# Connectors.net
KiCad netlist of a schematic drawn in Altium Designer
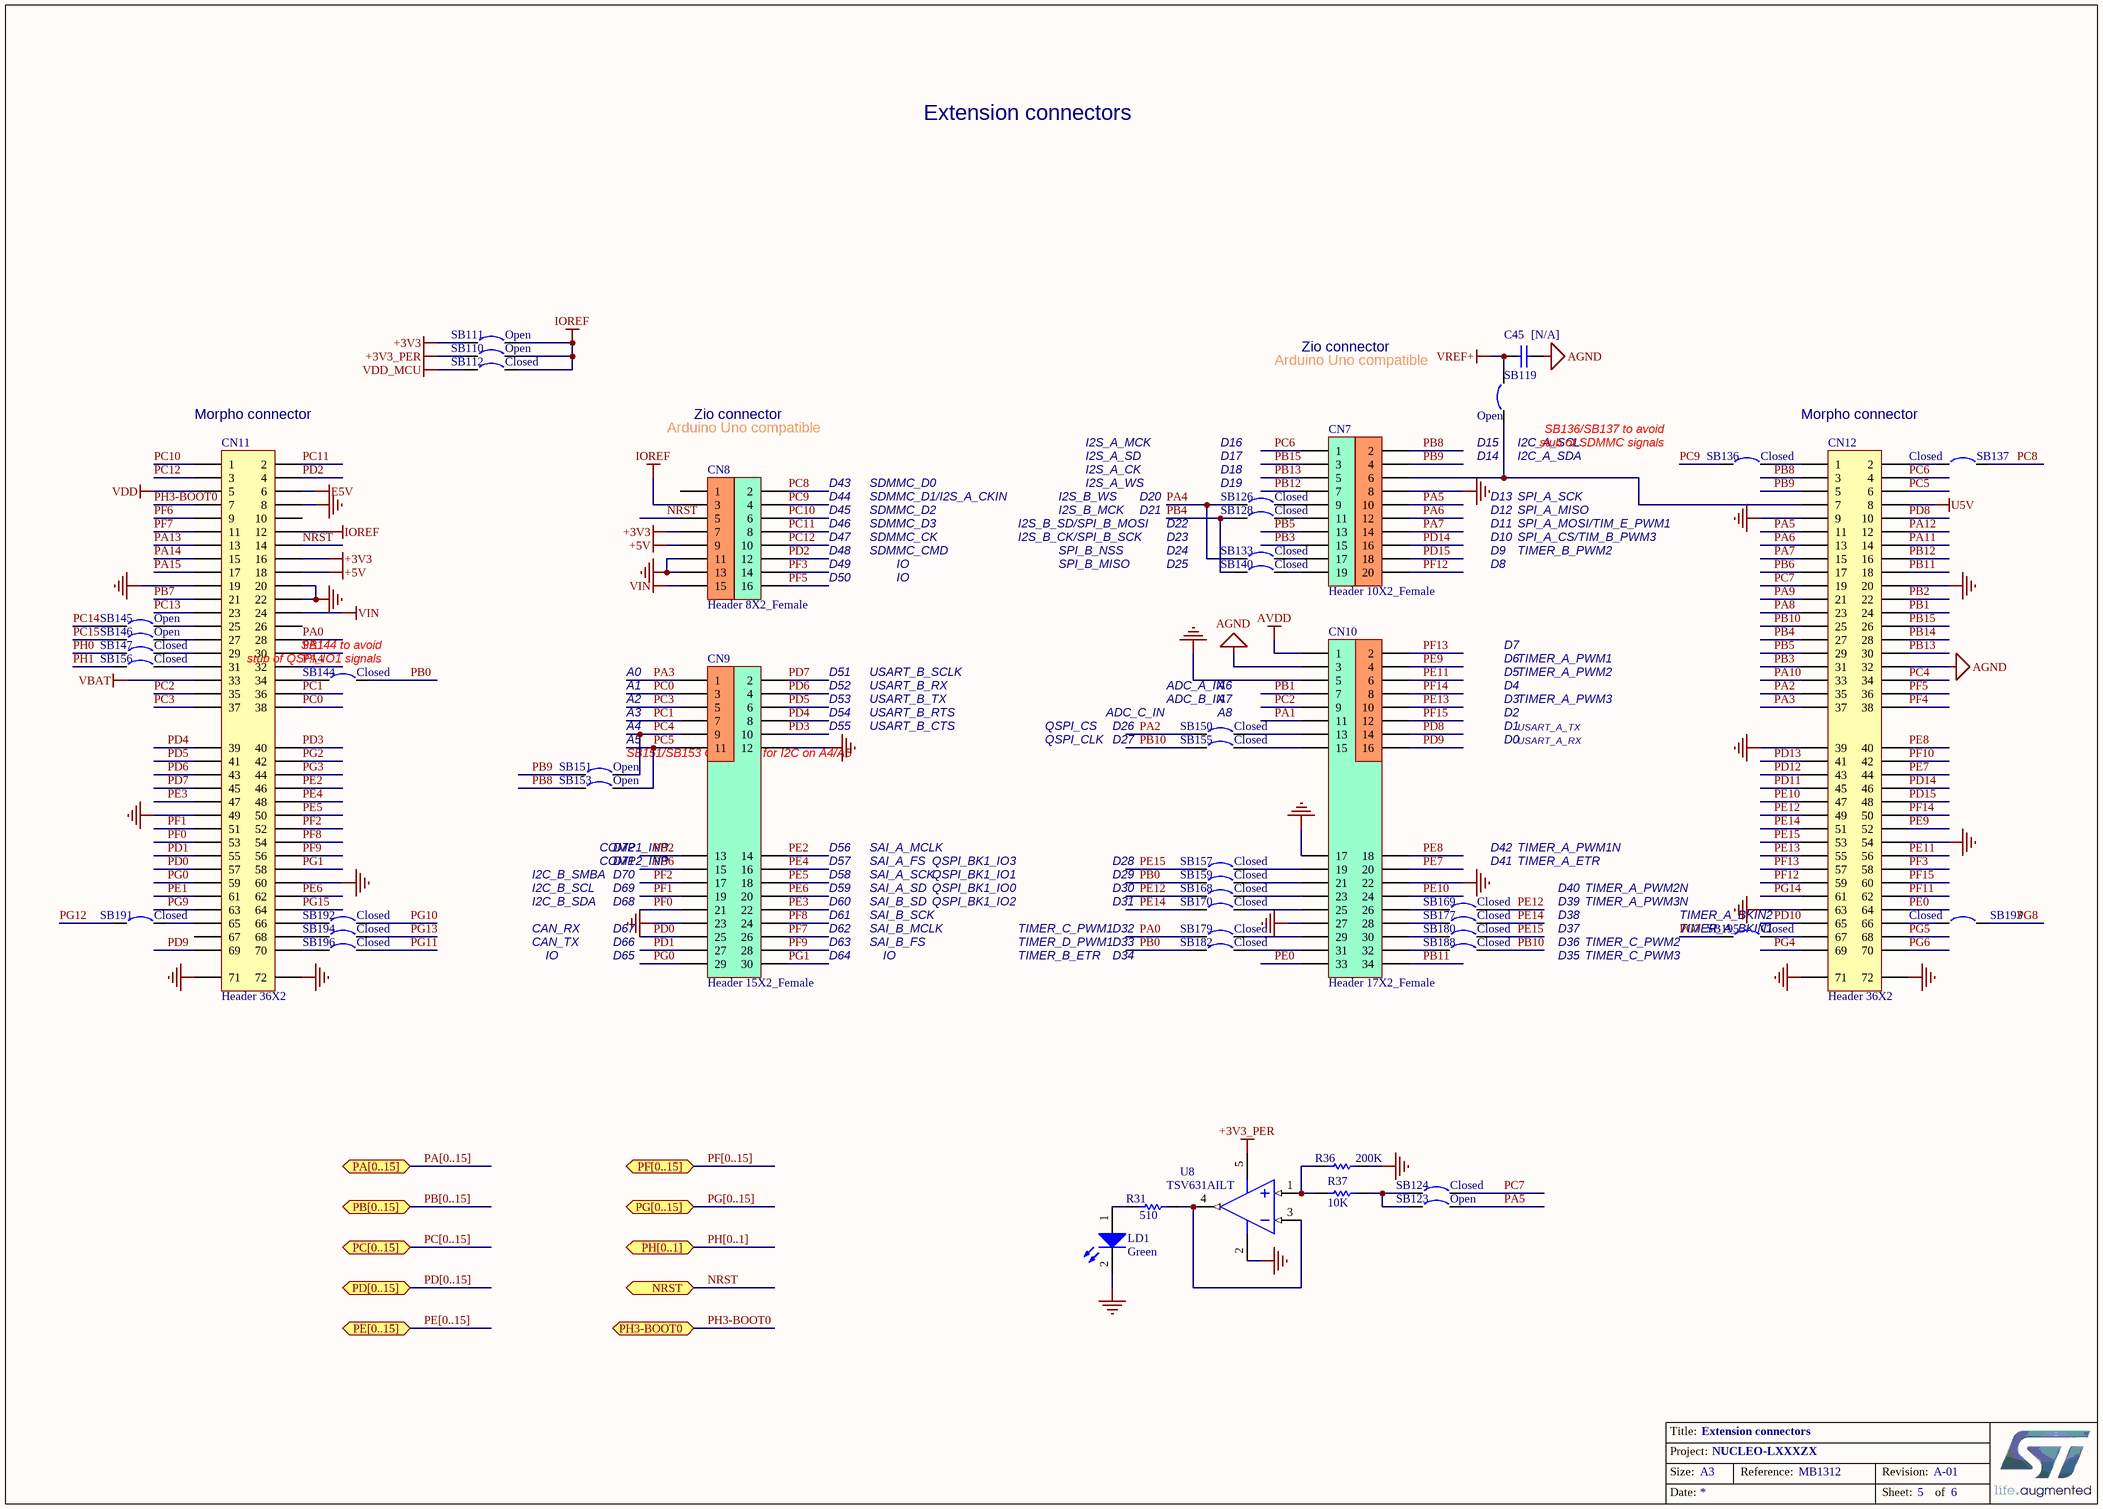
[diagram p0: Connectors.SchDoc]

(export (version "E")
  (design (tool "Eeschema 10.0.6"))
  (components
    (comp (ref "C45")
      (value "[N/A]")
      (footprint "0603C")
      (description "Capacitor,100nF,10%,16V,X7R,0603,YAGEO")
      (fields (field (name "PUBLISHER") "Altium Limited"))
      (libsource (lib "Miscellaneous Devices") (part "Cap"))
    )
    (comp (ref "CN7")
      (value "Header 10X2_Female")
      (footprint "HDR_10x2_2R54_V_F")
      (description "Header, 10-Pin, Dual row,female")
      (fields (field (name "PUBLISHER") "Altium Limited"))
      (libsource (lib "MB1137") (part "Header 10X2_Female"))
    )
    (comp (ref "CN8")
      (value "Header 8X2_Female")
      (footprint "HDR_8x2_2R54_V_F")
      (description "Header, 8-Pin, Dual row,female")
      (fields (field (name "PUBLISHER") "Altium Limited"))
      (libsource (lib "MB1137") (part "Header 8X2_Female"))
    )
    (comp (ref "CN9")
      (value "Header 15X2_Female")
      (footprint "HDR_15x2_2R54_V_F")
      (description "Header, 15-Pin, Dual row,female")
      (fields (field (name "PUBLISHER") "Altium Limited"))
      (libsource (lib "MB1137") (part "Header 15X2_Female"))
    )
    (comp (ref "CN10")
      (value "Header 17X2_Female")
      (footprint "HDR_17x2_2R54_V_F")
      (description "Header, 17-Pin, Dual row,female")
      (fields (field (name "PUBLISHER") "Altium Limited"))
      (libsource (lib "MB1137") (part "Header 17X2_Female"))
    )
    (comp (ref "CN11")
      (value "Header 36X2")
      (footprint "HDR_2x36_2R54_V_M")
      (description "Header, 36-Pin, Dual row")
      (fields (field (name "PUBLISHER") "Altium Limited"))
      (libsource (lib "MB1137") (part "Header 36X2"))
    )
    (comp (ref "CN12")
      (value "Header 36X2")
      (footprint "HDR_2x36_2R54_V_M")
      (description "Header, 36-Pin, Dual row")
      (fields (field (name "PUBLISHER") "Altium Limited"))
      (libsource (lib "MB1137") (part "Header 36X2"))
    )
    (comp (ref "LD1")
      (value "Green")
      (footprint "0603D-G")
      (description "Typical RED, GREEN, YELLOW, AMBER GaAs LED")
      (fields (field (name "PUBLISHER") "Altium Limited"))
      (libsource (lib "Miscellaneous Devices") (part "LED2"))
    )
    (comp (ref "R31")
      (value "510")
      (footprint "0603R")
      (description "Resistor")
      (fields (field (name "PUBLISHER") "Altium Limited"))
      (libsource (lib "Miscellaneous Devices") (part "Res1"))
    )
    (comp (ref "R36")
      (value "200K")
      (footprint "0603R")
      (description "Resistor")
      (fields (field (name "PUBLISHER") "Altium Limited"))
      (libsource (lib "Miscellaneous Devices") (part "res1"))
    )
    (comp (ref "R37")
      (value "10K")
      (footprint "0603R")
      (description "Resistor")
      (fields (field (name "PUBLISHER") "Altium Limited"))
      (libsource (lib "Miscellaneous Devices") (part "res1"))
    )
    (comp (ref "SB110")
      (value "Open")
      (footprint "SB_0603")
      (description "Circuit Breaker")
      (fields (field (name "PUBLISHER") "Altium Limited"))
      (libsource (lib "") (part "Circuit Breaker_1"))
    )
    (comp (ref "SB111")
      (value "Open")
      (footprint "SB_0603")
      (description "Circuit Breaker")
      (fields (field (name "PUBLISHER") "Altium Limited"))
      (libsource (lib "") (part "Circuit Breaker_1"))
    )
    (comp (ref "SB112")
      (value "Closed")
      (footprint "SB_0603")
      (description "Circuit Breaker")
      (fields (field (name "PUBLISHER") "Altium Limited"))
      (libsource (lib "MB1167") (part "Circuit Breaker_close"))
    )
    (comp (ref "SB119")
      (value "Open")
      (footprint "SB_0603")
      (description "Circuit Breaker")
      (fields (field (name "PUBLISHER") "Altium Limited"))
      (libsource (lib "MB1167") (part "Circuit Breaker"))
    )
    (comp (ref "SB123")
      (value "Open")
      (footprint "SB_0603")
      (description "Circuit Breaker")
      (fields (field (name "PUBLISHER") "Altium Limited"))
      (libsource (lib "") (part "Circuit Breaker_1"))
    )
    (comp (ref "SB124")
      (value "Closed")
      (footprint "SB_0603")
      (description "Circuit Breaker")
      (fields (field (name "PUBLISHER") "Altium Limited"))
      (libsource (lib "") (part "Circuit Breaker_close_1"))
    )
    (comp (ref "SB126")
      (value "Closed")
      (footprint "SB_0603")
      (description "Circuit Breaker")
      (fields (field (name "PUBLISHER") "Altium Limited"))
      (libsource (lib "MB1167") (part "Circuit Breaker_close"))
    )
    (comp (ref "SB128")
      (value "Closed")
      (footprint "SB_0603")
      (description "Circuit Breaker")
      (fields (field (name "PUBLISHER") "Altium Limited"))
      (libsource (lib "MB1167") (part "Circuit Breaker_close"))
    )
    (comp (ref "SB133")
      (value "Closed")
      (footprint "SB_0603")
      (description "Circuit Breaker")
      (fields (field (name "PUBLISHER") "Altium Limited"))
      (libsource (lib "MB1167") (part "Circuit Breaker_close"))
    )
    (comp (ref "SB136")
      (value "Closed")
      (footprint "SB_0603")
      (description "Circuit Breaker")
      (fields (field (name "PUBLISHER") "Altium Limited"))
      (libsource (lib "MB1167") (part "Circuit Breaker_close"))
    )
    (comp (ref "SB137")
      (value "Closed")
      (footprint "SB_0603")
      (description "Circuit Breaker")
      (fields (field (name "PUBLISHER") "Altium Limited"))
      (libsource (lib "") (part "Circuit Breaker_close_1"))
    )
    (comp (ref "SB140")
      (value "Closed")
      (footprint "SB_0603")
      (description "Circuit Breaker")
      (fields (field (name "PUBLISHER") "Altium Limited"))
      (libsource (lib "MB1167") (part "Circuit Breaker_close"))
    )
    (comp (ref "SB144")
      (value "Closed")
      (footprint "SB_0603")
      (description "Circuit Breaker")
      (fields (field (name "PUBLISHER") "Altium Limited"))
      (libsource (lib "MB1167") (part "Circuit Breaker_close"))
    )
    (comp (ref "SB145")
      (value "Open")
      (footprint "SB_0603")
      (description "Circuit Breaker")
      (fields (field (name "PUBLISHER") "Altium Limited"))
      (libsource (lib "") (part "Circuit Breaker_1"))
    )
    (comp (ref "SB146")
      (value "Open")
      (footprint "SB_0603")
      (description "Circuit Breaker")
      (fields (field (name "PUBLISHER") "Altium Limited"))
      (libsource (lib "") (part "Circuit Breaker_1"))
    )
    (comp (ref "SB147")
      (value "Closed")
      (footprint "SB_0603")
      (description "Circuit Breaker")
      (fields (field (name "PUBLISHER") "Altium Limited"))
      (libsource (lib "MB1167") (part "Circuit Breaker_close"))
    )
    (comp (ref "SB150")
      (value "Closed")
      (footprint "SB_0603")
      (description "Circuit Breaker")
      (fields (field (name "PUBLISHER") "Altium Limited"))
      (libsource (lib "MB1167") (part "Circuit Breaker_close"))
    )
    (comp (ref "SB151")
      (value "Open")
      (footprint "SB_0603")
      (description "Circuit Breaker")
      (fields (field (name "PUBLISHER") "Altium Limited"))
      (libsource (lib "") (part "Circuit Breaker_2"))
    )
    (comp (ref "SB153")
      (value "Open")
      (footprint "SB_0603")
      (description "Circuit Breaker")
      (fields (field (name "PUBLISHER") "Altium Limited"))
      (libsource (lib "") (part "Circuit Breaker_2"))
    )
    (comp (ref "SB155")
      (value "Closed")
      (footprint "SB_0603")
      (description "Circuit Breaker")
      (fields (field (name "PUBLISHER") "Altium Limited"))
      (libsource (lib "MB1167") (part "Circuit Breaker_close"))
    )
    (comp (ref "SB156")
      (value "Closed")
      (footprint "SB_0603")
      (description "Circuit Breaker")
      (fields (field (name "PUBLISHER") "Altium Limited"))
      (libsource (lib "MB1167") (part "Circuit Breaker_close"))
    )
    (comp (ref "SB157")
      (value "Closed")
      (footprint "SB_0603")
      (description "Circuit Breaker")
      (fields (field (name "PUBLISHER") "Altium Limited"))
      (libsource (lib "MB1167") (part "Circuit Breaker_close"))
    )
    (comp (ref "SB159")
      (value "Closed")
      (footprint "SB_0603")
      (description "Circuit Breaker")
      (fields (field (name "PUBLISHER") "Altium Limited"))
      (libsource (lib "MB1167") (part "Circuit Breaker_close"))
    )
    (comp (ref "SB168")
      (value "Closed")
      (footprint "SB_0603")
      (description "Circuit Breaker")
      (fields (field (name "PUBLISHER") "Altium Limited"))
      (libsource (lib "MB1167") (part "Circuit Breaker_close"))
    )
    (comp (ref "SB169")
      (value "Closed")
      (footprint "SB_0603")
      (description "Circuit Breaker")
      (fields (field (name "PUBLISHER") "Altium Limited"))
      (libsource (lib "MB1167") (part "Circuit Breaker_close"))
    )
    (comp (ref "SB170")
      (value "Closed")
      (footprint "SB_0603")
      (description "Circuit Breaker")
      (fields (field (name "PUBLISHER") "Altium Limited"))
      (libsource (lib "MB1167") (part "Circuit Breaker_close"))
    )
    (comp (ref "SB177")
      (value "Closed")
      (footprint "SB_0603")
      (description "Circuit Breaker")
      (fields (field (name "PUBLISHER") "Altium Limited"))
      (libsource (lib "MB1167") (part "Circuit Breaker_close"))
    )
    (comp (ref "SB179")
      (value "Closed")
      (footprint "SB_0603")
      (description "Circuit Breaker")
      (fields (field (name "PUBLISHER") "Altium Limited"))
      (libsource (lib "MB1167") (part "Circuit Breaker_close"))
    )
    (comp (ref "SB180")
      (value "Closed")
      (footprint "SB_0603")
      (description "Circuit Breaker")
      (fields (field (name "PUBLISHER") "Altium Limited"))
      (libsource (lib "MB1167") (part "Circuit Breaker_close"))
    )
    (comp (ref "SB182")
      (value "Closed")
      (footprint "SB_0603")
      (description "Circuit Breaker")
      (fields (field (name "PUBLISHER") "Altium Limited"))
      (libsource (lib "MB1167") (part "Circuit Breaker_close"))
    )
    (comp (ref "SB188")
      (value "Closed")
      (footprint "SB_0603")
      (description "Circuit Breaker")
      (fields (field (name "PUBLISHER") "Altium Limited"))
      (libsource (lib "MB1167") (part "Circuit Breaker_close"))
    )
    (comp (ref "SB191")
      (value "Closed")
      (footprint "SB_0603")
      (description "Circuit Breaker")
      (fields (field (name "PUBLISHER") "Altium Limited"))
      (libsource (lib "MB1167") (part "Circuit Breaker_close"))
    )
    (comp (ref "SB192")
      (value "Closed")
      (footprint "SB_0603")
      (description "Circuit Breaker")
      (fields (field (name "PUBLISHER") "Altium Limited"))
      (libsource (lib "MB1167") (part "Circuit Breaker_close"))
    )
    (comp (ref "SB193")
      (value "Closed")
      (footprint "SB_0603")
      (description "Circuit Breaker")
      (fields (field (name "PUBLISHER") "Altium Limited"))
      (libsource (lib "MB1167") (part "Circuit Breaker_close"))
    )
    (comp (ref "SB194")
      (value "Closed")
      (footprint "SB_0603")
      (description "Circuit Breaker")
      (fields (field (name "PUBLISHER") "Altium Limited"))
      (libsource (lib "MB1167") (part "Circuit Breaker_close"))
    )
    (comp (ref "SB195")
      (value "Closed")
      (footprint "SB_0603")
      (description "Circuit Breaker")
      (fields (field (name "PUBLISHER") "Altium Limited"))
      (libsource (lib "MB1167") (part "Circuit Breaker_close"))
    )
    (comp (ref "SB196")
      (value "Closed")
      (footprint "SB_0603")
      (description "Circuit Breaker")
      (fields (field (name "PUBLISHER") "Altium Limited"))
      (libsource (lib "MB1167") (part "Circuit Breaker_close"))
    )
    (comp (ref "U8")
      (value "TSV631AILT")
      (footprint "SOT-23-5L")
      (libsource (lib "MB988") (part "TSV631AILT"))
    )
  )
  (nets
    (net (code "1") (name "+3V3") (class "Default")
      (node (ref "CN11") (pin "16") (pinfunction "16_16") (pintype "passive"))
      (node (ref "CN8") (pin "7") (pinfunction "7_7") (pintype "passive"))
      (node (ref "SB111") (pin "1") (pinfunction "1_1") (pintype "passive"))
    )
    (net (code "2") (name "+3V3_PER") (class "Default")
      (node (ref "SB110") (pin "1") (pinfunction "1_1") (pintype "passive"))
      (node (ref "U8") (pin "5") (pinfunction "VCC_5") (pintype "power_in"))
    )
    (net (code "3") (name "+5V") (class "Default")
      (node (ref "CN11") (pin "18") (pinfunction "18_18") (pintype "passive"))
      (node (ref "CN8") (pin "9") (pinfunction "9_9") (pintype "passive"))
    )
    (net (code "4") (name "/NRST") (class "Default")
      (node (ref "CN11") (pin "14") (pinfunction "14_14") (pintype "passive"))
      (node (ref "CN8") (pin "5") (pinfunction "5_5") (pintype "passive"))
    )
    (net (code "5") (name "/PA0") (class "Default")
      (node (ref "CN11") (pin "28") (pinfunction "28_28") (pintype "passive"))
      (node (ref "SB179") (pin "1") (pinfunction "1_1") (pintype "passive"))
    )
    (net (code "6") (name "/PA1") (class "Default")
      (node (ref "CN10") (pin "11") (pinfunction "11_11") (pintype "passive"))
      (node (ref "CN11") (pin "30") (pinfunction "30_30") (pintype "passive"))
    )
    (net (code "7") (name "/PA2") (class "Default")
      (node (ref "CN12") (pin "35") (pinfunction "35_35") (pintype "passive"))
      (node (ref "SB150") (pin "1") (pinfunction "1_1") (pintype "passive"))
    )
    (net (code "8") (name "/PA3") (class "Default")
      (node (ref "CN12") (pin "37") (pinfunction "37_37") (pintype "passive"))
      (node (ref "CN9") (pin "1") (pinfunction "1_1") (pintype "passive"))
    )
    (net (code "9") (name "/PA4") (class "Default")
      (node (ref "CN11") (pin "32") (pinfunction "32_32") (pintype "passive"))
      (node (ref "SB126") (pin "1") (pinfunction "1_1") (pintype "passive"))
      (node (ref "SB133") (pin "1") (pinfunction "1_1") (pintype "passive"))
    )
    (net (code "10") (name "/PA5") (class "Default")
      (node (ref "CN12") (pin "11") (pinfunction "11_11") (pintype "passive"))
      (node (ref "CN7") (pin "10") (pinfunction "10_10") (pintype "passive"))
      (node (ref "SB123") (pin "2") (pinfunction "2_2") (pintype "passive"))
    )
    (net (code "11") (name "/PA6") (class "Default")
      (node (ref "CN12") (pin "13") (pinfunction "13_13") (pintype "passive"))
      (node (ref "CN7") (pin "12") (pinfunction "12_12") (pintype "passive"))
    )
    (net (code "12") (name "/PA7") (class "Default")
      (node (ref "CN12") (pin "15") (pinfunction "15_15") (pintype "passive"))
      (node (ref "CN7") (pin "14") (pinfunction "14_14") (pintype "passive"))
    )
    (net (code "13") (name "/PA8") (class "Default")
      (node (ref "CN12") (pin "23") (pinfunction "23_23") (pintype "passive"))
    )
    (net (code "14") (name "/PA9") (class "Default")
      (node (ref "CN12") (pin "21") (pinfunction "21_21") (pintype "passive"))
    )
    (net (code "15") (name "/PA10") (class "Default")
      (node (ref "CN12") (pin "33") (pinfunction "33_33") (pintype "passive"))
    )
    (net (code "16") (name "/PA11") (class "Default")
      (node (ref "CN12") (pin "14") (pinfunction "14_14") (pintype "passive"))
    )
    (net (code "17") (name "/PA12") (class "Default")
      (node (ref "CN12") (pin "12") (pinfunction "12_12") (pintype "passive"))
    )
    (net (code "18") (name "/PA13") (class "Default")
      (node (ref "CN11") (pin "13") (pinfunction "13_13") (pintype "passive"))
    )
    (net (code "19") (name "/PA14") (class "Default")
      (node (ref "CN11") (pin "15") (pinfunction "15_15") (pintype "passive"))
    )
    (net (code "20") (name "/PA15") (class "Default")
      (node (ref "CN11") (pin "17") (pinfunction "17_17") (pintype "passive"))
    )
    (net (code "22") (name "/PB0") (class "Default")
      (node (ref "SB144") (pin "2") (pinfunction "2_2") (pintype "passive"))
      (node (ref "SB159") (pin "1") (pinfunction "1_1") (pintype "passive"))
      (node (ref "SB182") (pin "1") (pinfunction "1_1") (pintype "passive"))
    )
    (net (code "23") (name "/PB1") (class "Default")
      (node (ref "CN10") (pin "7") (pinfunction "7_7") (pintype "passive"))
      (node (ref "CN12") (pin "24") (pinfunction "24_24") (pintype "passive"))
    )
    (net (code "24") (name "/PB2") (class "Default")
      (node (ref "CN12") (pin "22") (pinfunction "22_22") (pintype "passive"))
      (node (ref "CN9") (pin "13") (pinfunction "13_13") (pintype "passive"))
    )
    (net (code "25") (name "/PB3") (class "Default")
      (node (ref "CN12") (pin "31") (pinfunction "31_31") (pintype "passive"))
      (node (ref "CN7") (pin "15") (pinfunction "15_15") (pintype "passive"))
    )
    (net (code "26") (name "/PB4") (class "Default")
      (node (ref "CN12") (pin "27") (pinfunction "27_27") (pintype "passive"))
      (node (ref "SB128") (pin "1") (pinfunction "1_1") (pintype "passive"))
      (node (ref "SB140") (pin "1") (pinfunction "1_1") (pintype "passive"))
    )
    (net (code "27") (name "/PB5") (class "Default")
      (node (ref "CN12") (pin "29") (pinfunction "29_29") (pintype "passive"))
      (node (ref "CN7") (pin "13") (pinfunction "13_13") (pintype "passive"))
    )
    (net (code "28") (name "/PB6") (class "Default")
      (node (ref "CN12") (pin "17") (pinfunction "17_17") (pintype "passive"))
      (node (ref "CN9") (pin "15") (pinfunction "15_15") (pintype "passive"))
    )
    (net (code "29") (name "/PB7") (class "Default")
      (node (ref "CN11") (pin "21") (pinfunction "21_21") (pintype "passive"))
    )
    (net (code "30") (name "/PB8") (class "Default")
      (node (ref "CN12") (pin "3") (pinfunction "3_3") (pintype "passive"))
      (node (ref "CN7") (pin "2") (pinfunction "2_2") (pintype "passive"))
      (node (ref "SB153") (pin "2") (pinfunction "2_2") (pintype "passive"))
    )
    (net (code "31") (name "/PB9") (class "Default")
      (node (ref "CN12") (pin "5") (pinfunction "5_5") (pintype "passive"))
      (node (ref "CN7") (pin "4") (pinfunction "4_4") (pintype "passive"))
      (node (ref "SB151") (pin "2") (pinfunction "2_2") (pintype "passive"))
    )
    (net (code "32") (name "/PB10") (class "Default")
      (node (ref "CN12") (pin "25") (pinfunction "25_25") (pintype "passive"))
      (node (ref "SB155") (pin "1") (pinfunction "1_1") (pintype "passive"))
      (node (ref "SB188") (pin "2") (pinfunction "2_2") (pintype "passive"))
    )
    (net (code "33") (name "/PB11") (class "Default")
      (node (ref "CN10") (pin "34") (pinfunction "34_34") (pintype "passive"))
      (node (ref "CN12") (pin "18") (pinfunction "18_18") (pintype "passive"))
    )
    (net (code "34") (name "/PB12") (class "Default")
      (node (ref "CN12") (pin "16") (pinfunction "16_16") (pintype "passive"))
      (node (ref "CN7") (pin "7") (pinfunction "7_7") (pintype "passive"))
    )
    (net (code "35") (name "/PB13") (class "Default")
      (node (ref "CN12") (pin "30") (pinfunction "30_30") (pintype "passive"))
      (node (ref "CN7") (pin "5") (pinfunction "5_5") (pintype "passive"))
    )
    (net (code "36") (name "/PB14") (class "Default")
      (node (ref "CN12") (pin "28") (pinfunction "28_28") (pintype "passive"))
    )
    (net (code "37") (name "/PB15") (class "Default")
      (node (ref "CN12") (pin "26") (pinfunction "26_26") (pintype "passive"))
      (node (ref "CN7") (pin "3") (pinfunction "3_3") (pintype "passive"))
    )
    (net (code "39") (name "/PC0") (class "Default")
      (node (ref "CN11") (pin "38") (pinfunction "38_38") (pintype "passive"))
      (node (ref "CN9") (pin "3") (pinfunction "3_3") (pintype "passive"))
    )
    (net (code "40") (name "/PC1") (class "Default")
      (node (ref "CN11") (pin "36") (pinfunction "36_36") (pintype "passive"))
      (node (ref "CN9") (pin "7") (pinfunction "7_7") (pintype "passive"))
    )
    (net (code "41") (name "/PC2") (class "Default")
      (node (ref "CN10") (pin "9") (pinfunction "9_9") (pintype "passive"))
      (node (ref "CN11") (pin "35") (pinfunction "35_35") (pintype "passive"))
    )
    (net (code "42") (name "/PC3") (class "Default")
      (node (ref "CN11") (pin "37") (pinfunction "37_37") (pintype "passive"))
      (node (ref "CN9") (pin "5") (pinfunction "5_5") (pintype "passive"))
    )
    (net (code "43") (name "/PC4") (class "Default")
      (node (ref "CN12") (pin "34") (pinfunction "34_34") (pintype "passive"))
      (node (ref "CN9") (pin "9") (pinfunction "9_9") (pintype "passive"))
      (node (ref "SB151") (pin "1") (pinfunction "1_1") (pintype "passive"))
    )
    (net (code "44") (name "/PC5") (class "Default")
      (node (ref "CN12") (pin "6") (pinfunction "6_6") (pintype "passive"))
      (node (ref "CN9") (pin "11") (pinfunction "11_11") (pintype "passive"))
      (node (ref "SB153") (pin "1") (pinfunction "1_1") (pintype "passive"))
    )
    (net (code "45") (name "/PC6") (class "Default")
      (node (ref "CN12") (pin "4") (pinfunction "4_4") (pintype "passive"))
      (node (ref "CN7") (pin "1") (pinfunction "1_1") (pintype "passive"))
    )
    (net (code "46") (name "/PC7") (class "Default")
      (node (ref "CN12") (pin "19") (pinfunction "19_19") (pintype "passive"))
      (node (ref "SB124") (pin "1") (pinfunction "1_1") (pintype "passive"))
    )
    (net (code "47") (name "/PC8") (class "Default")
      (node (ref "CN8") (pin "2") (pinfunction "2_2") (pintype "passive"))
      (node (ref "SB137") (pin "1") (pinfunction "1_1") (pintype "passive"))
    )
    (net (code "48") (name "/PC9") (class "Default")
      (node (ref "CN8") (pin "4") (pinfunction "4_4") (pintype "passive"))
      (node (ref "SB136") (pin "1") (pinfunction "1_1") (pintype "passive"))
    )
    (net (code "49") (name "/PC10") (class "Default")
      (node (ref "CN11") (pin "1") (pinfunction "1_1") (pintype "passive"))
      (node (ref "CN8") (pin "6") (pinfunction "6_6") (pintype "passive"))
    )
    (net (code "50") (name "/PC11") (class "Default")
      (node (ref "CN11") (pin "2") (pinfunction "2_2") (pintype "passive"))
      (node (ref "CN8") (pin "8") (pinfunction "8_8") (pintype "passive"))
    )
    (net (code "51") (name "/PC12") (class "Default")
      (node (ref "CN11") (pin "3") (pinfunction "3_3") (pintype "passive"))
      (node (ref "CN8") (pin "10") (pinfunction "10_10") (pintype "passive"))
    )
    (net (code "52") (name "/PC13") (class "Default")
      (node (ref "CN11") (pin "23") (pinfunction "23_23") (pintype "passive"))
    )
    (net (code "53") (name "/PC14") (class "Default")
      (node (ref "SB145") (pin "1") (pinfunction "1_1") (pintype "passive"))
    )
    (net (code "54") (name "/PC15") (class "Default")
      (node (ref "SB146") (pin "1") (pinfunction "1_1") (pintype "passive"))
    )
    (net (code "56") (name "/PD0") (class "Default")
      (node (ref "CN11") (pin "57") (pinfunction "57_57") (pintype "passive"))
      (node (ref "CN9") (pin "25") (pinfunction "25_25") (pintype "passive"))
    )
    (net (code "57") (name "/PD1") (class "Default")
      (node (ref "CN11") (pin "55") (pinfunction "55_55") (pintype "passive"))
      (node (ref "CN9") (pin "27") (pinfunction "27_27") (pintype "passive"))
    )
    (net (code "58") (name "/PD2") (class "Default")
      (node (ref "CN11") (pin "4") (pinfunction "4_4") (pintype "passive"))
      (node (ref "CN8") (pin "12") (pinfunction "12_12") (pintype "passive"))
    )
    (net (code "59") (name "/PD3") (class "Default")
      (node (ref "CN11") (pin "40") (pinfunction "40_40") (pintype "passive"))
      (node (ref "CN9") (pin "10") (pinfunction "10_10") (pintype "passive"))
    )
    (net (code "60") (name "/PD4") (class "Default")
      (node (ref "CN11") (pin "39") (pinfunction "39_39") (pintype "passive"))
      (node (ref "CN9") (pin "8") (pinfunction "8_8") (pintype "passive"))
    )
    (net (code "61") (name "/PD5") (class "Default")
      (node (ref "CN11") (pin "41") (pinfunction "41_41") (pintype "passive"))
      (node (ref "CN9") (pin "6") (pinfunction "6_6") (pintype "passive"))
    )
    (net (code "62") (name "/PD6") (class "Default")
      (node (ref "CN11") (pin "43") (pinfunction "43_43") (pintype "passive"))
      (node (ref "CN9") (pin "4") (pinfunction "4_4") (pintype "passive"))
    )
    (net (code "63") (name "/PD7") (class "Default")
      (node (ref "CN11") (pin "45") (pinfunction "45_45") (pintype "passive"))
      (node (ref "CN9") (pin "2") (pinfunction "2_2") (pintype "passive"))
    )
    (net (code "64") (name "/PD8") (class "Default")
      (node (ref "CN10") (pin "14") (pinfunction "14_14") (pintype "passive"))
      (node (ref "CN12") (pin "10") (pinfunction "10_10") (pintype "passive"))
    )
    (net (code "65") (name "/PD9") (class "Default")
      (node (ref "CN10") (pin "16") (pinfunction "16_16") (pintype "passive"))
      (node (ref "CN11") (pin "69") (pinfunction "69_69") (pintype "passive"))
    )
    (net (code "66") (name "/PD10") (class "Default")
      (node (ref "CN12") (pin "65") (pinfunction "65_65") (pintype "passive"))
    )
    (net (code "67") (name "/PD11") (class "Default")
      (node (ref "CN12") (pin "45") (pinfunction "45_45") (pintype "passive"))
    )
    (net (code "68") (name "/PD12") (class "Default")
      (node (ref "CN12") (pin "43") (pinfunction "43_43") (pintype "passive"))
    )
    (net (code "69") (name "/PD13") (class "Default")
      (node (ref "CN12") (pin "41") (pinfunction "41_41") (pintype "passive"))
    )
    (net (code "70") (name "/PD14") (class "Default")
      (node (ref "CN12") (pin "46") (pinfunction "46_46") (pintype "passive"))
      (node (ref "CN7") (pin "16") (pinfunction "16_16") (pintype "passive"))
    )
    (net (code "71") (name "/PD15") (class "Default")
      (node (ref "CN12") (pin "48") (pinfunction "48_48") (pintype "passive"))
      (node (ref "CN7") (pin "18") (pinfunction "18_18") (pintype "passive"))
    )
    (net (code "73") (name "/PE0") (class "Default")
      (node (ref "CN10") (pin "33") (pinfunction "33_33") (pintype "passive"))
      (node (ref "CN12") (pin "64") (pinfunction "64_64") (pintype "passive"))
    )
    (net (code "74") (name "/PE1") (class "Default")
      (node (ref "CN11") (pin "61") (pinfunction "61_61") (pintype "passive"))
    )
    (net (code "75") (name "/PE2") (class "Default")
      (node (ref "CN11") (pin "46") (pinfunction "46_46") (pintype "passive"))
      (node (ref "CN9") (pin "14") (pinfunction "14_14") (pintype "passive"))
    )
    (net (code "76") (name "/PE3") (class "Default")
      (node (ref "CN11") (pin "47") (pinfunction "47_47") (pintype "passive"))
      (node (ref "CN9") (pin "22") (pinfunction "22_22") (pintype "passive"))
    )
    (net (code "77") (name "/PE4") (class "Default")
      (node (ref "CN11") (pin "48") (pinfunction "48_48") (pintype "passive"))
      (node (ref "CN9") (pin "16") (pinfunction "16_16") (pintype "passive"))
    )
    (net (code "78") (name "/PE5") (class "Default")
      (node (ref "CN11") (pin "50") (pinfunction "50_50") (pintype "passive"))
      (node (ref "CN9") (pin "18") (pinfunction "18_18") (pintype "passive"))
    )
    (net (code "79") (name "/PE6") (class "Default")
      (node (ref "CN11") (pin "62") (pinfunction "62_62") (pintype "passive"))
      (node (ref "CN9") (pin "20") (pinfunction "20_20") (pintype "passive"))
    )
    (net (code "80") (name "/PE7") (class "Default")
      (node (ref "CN10") (pin "20") (pinfunction "20_20") (pintype "passive"))
      (node (ref "CN12") (pin "44") (pinfunction "44_44") (pintype "passive"))
    )
    (net (code "81") (name "/PE8") (class "Default")
      (node (ref "CN10") (pin "18") (pinfunction "18_18") (pintype "passive"))
      (node (ref "CN12") (pin "40") (pinfunction "40_40") (pintype "passive"))
    )
    (net (code "82") (name "/PE9") (class "Default")
      (node (ref "CN10") (pin "4") (pinfunction "4_4") (pintype "passive"))
      (node (ref "CN12") (pin "52") (pinfunction "52_52") (pintype "passive"))
    )
    (net (code "83") (name "/PE10") (class "Default")
      (node (ref "CN10") (pin "24") (pinfunction "24_24") (pintype "passive"))
      (node (ref "CN12") (pin "47") (pinfunction "47_47") (pintype "passive"))
    )
    (net (code "84") (name "/PE11") (class "Default")
      (node (ref "CN10") (pin "6") (pinfunction "6_6") (pintype "passive"))
      (node (ref "CN12") (pin "56") (pinfunction "56_56") (pintype "passive"))
    )
    (net (code "85") (name "/PE12") (class "Default")
      (node (ref "CN12") (pin "49") (pinfunction "49_49") (pintype "passive"))
      (node (ref "SB168") (pin "1") (pinfunction "1_1") (pintype "passive"))
      (node (ref "SB169") (pin "2") (pinfunction "2_2") (pintype "passive"))
    )
    (net (code "86") (name "/PE13") (class "Default")
      (node (ref "CN10") (pin "10") (pinfunction "10_10") (pintype "passive"))
      (node (ref "CN12") (pin "55") (pinfunction "55_55") (pintype "passive"))
    )
    (net (code "87") (name "/PE14") (class "Default")
      (node (ref "CN12") (pin "51") (pinfunction "51_51") (pintype "passive"))
      (node (ref "SB170") (pin "1") (pinfunction "1_1") (pintype "passive"))
      (node (ref "SB177") (pin "2") (pinfunction "2_2") (pintype "passive"))
    )
    (net (code "88") (name "/PE15") (class "Default")
      (node (ref "CN12") (pin "53") (pinfunction "53_53") (pintype "passive"))
      (node (ref "SB157") (pin "1") (pinfunction "1_1") (pintype "passive"))
      (node (ref "SB180") (pin "2") (pinfunction "2_2") (pintype "passive"))
    )
    (net (code "90") (name "/PF0") (class "Default")
      (node (ref "CN11") (pin "53") (pinfunction "53_53") (pintype "passive"))
      (node (ref "CN9") (pin "21") (pinfunction "21_21") (pintype "passive"))
    )
    (net (code "91") (name "/PF1") (class "Default")
      (node (ref "CN11") (pin "51") (pinfunction "51_51") (pintype "passive"))
      (node (ref "CN9") (pin "19") (pinfunction "19_19") (pintype "passive"))
    )
    (net (code "92") (name "/PF2") (class "Default")
      (node (ref "CN11") (pin "52") (pinfunction "52_52") (pintype "passive"))
      (node (ref "CN9") (pin "17") (pinfunction "17_17") (pintype "passive"))
    )
    (net (code "93") (name "/PF3") (class "Default")
      (node (ref "CN12") (pin "58") (pinfunction "58_58") (pintype "passive"))
      (node (ref "CN8") (pin "14") (pinfunction "14_14") (pintype "passive"))
    )
    (net (code "94") (name "/PF4") (class "Default")
      (node (ref "CN12") (pin "38") (pinfunction "38_38") (pintype "passive"))
    )
    (net (code "95") (name "/PF5") (class "Default")
      (node (ref "CN12") (pin "36") (pinfunction "36_36") (pintype "passive"))
      (node (ref "CN8") (pin "16") (pinfunction "16_16") (pintype "passive"))
    )
    (net (code "96") (name "/PF6") (class "Default")
      (node (ref "CN11") (pin "9") (pinfunction "9_9") (pintype "passive"))
    )
    (net (code "97") (name "/PF7") (class "Default")
      (node (ref "CN11") (pin "11") (pinfunction "11_11") (pintype "passive"))
      (node (ref "CN9") (pin "26") (pinfunction "26_26") (pintype "passive"))
    )
    (net (code "98") (name "/PF8") (class "Default")
      (node (ref "CN11") (pin "54") (pinfunction "54_54") (pintype "passive"))
      (node (ref "CN9") (pin "24") (pinfunction "24_24") (pintype "passive"))
    )
    (net (code "99") (name "/PF9") (class "Default")
      (node (ref "CN11") (pin "56") (pinfunction "56_56") (pintype "passive"))
      (node (ref "CN9") (pin "28") (pinfunction "28_28") (pintype "passive"))
    )
    (net (code "100") (name "/PF10") (class "Default")
      (node (ref "CN12") (pin "42") (pinfunction "42_42") (pintype "passive"))
    )
    (net (code "101") (name "/PF11") (class "Default")
      (node (ref "CN12") (pin "62") (pinfunction "62_62") (pintype "passive"))
    )
    (net (code "102") (name "/PF12") (class "Default")
      (node (ref "CN12") (pin "59") (pinfunction "59_59") (pintype "passive"))
      (node (ref "CN7") (pin "20") (pinfunction "20_20") (pintype "passive"))
    )
    (net (code "103") (name "/PF13") (class "Default")
      (node (ref "CN10") (pin "2") (pinfunction "2_2") (pintype "passive"))
      (node (ref "CN12") (pin "57") (pinfunction "57_57") (pintype "passive"))
    )
    (net (code "104") (name "/PF14") (class "Default")
      (node (ref "CN10") (pin "8") (pinfunction "8_8") (pintype "passive"))
      (node (ref "CN12") (pin "50") (pinfunction "50_50") (pintype "passive"))
    )
    (net (code "105") (name "/PF15") (class "Default")
      (node (ref "CN10") (pin "12") (pinfunction "12_12") (pintype "passive"))
      (node (ref "CN12") (pin "60") (pinfunction "60_60") (pintype "passive"))
    )
    (net (code "107") (name "/PG0") (class "Default")
      (node (ref "CN11") (pin "59") (pinfunction "59_59") (pintype "passive"))
      (node (ref "CN9") (pin "29") (pinfunction "29_29") (pintype "passive"))
    )
    (net (code "108") (name "/PG1") (class "Default")
      (node (ref "CN11") (pin "58") (pinfunction "58_58") (pintype "passive"))
      (node (ref "CN9") (pin "30") (pinfunction "30_30") (pintype "passive"))
    )
    (net (code "109") (name "/PG2") (class "Default")
      (node (ref "CN11") (pin "42") (pinfunction "42_42") (pintype "passive"))
    )
    (net (code "110") (name "/PG3") (class "Default")
      (node (ref "CN11") (pin "44") (pinfunction "44_44") (pintype "passive"))
    )
    (net (code "111") (name "/PG4") (class "Default")
      (node (ref "CN12") (pin "69") (pinfunction "69_69") (pintype "passive"))
    )
    (net (code "112") (name "/PG5") (class "Default")
      (node (ref "CN12") (pin "68") (pinfunction "68_68") (pintype "passive"))
    )
    (net (code "113") (name "/PG6") (class "Default")
      (node (ref "CN12") (pin "70") (pinfunction "70_70") (pintype "passive"))
    )
    (net (code "114") (name "/PG7") (class "Default")
      (node (ref "SB195") (pin "1") (pinfunction "1_1") (pintype "passive"))
    )
    (net (code "115") (name "/PG8") (class "Default")
      (node (ref "SB193") (pin "2") (pinfunction "2_2") (pintype "passive"))
    )
    (net (code "116") (name "/PG9") (class "Default")
      (node (ref "CN11") (pin "63") (pinfunction "63_63") (pintype "passive"))
    )
    (net (code "117") (name "/PG10") (class "Default")
      (node (ref "SB192") (pin "2") (pinfunction "2_2") (pintype "passive"))
    )
    (net (code "118") (name "/PG11") (class "Default")
      (node (ref "SB196") (pin "2") (pinfunction "2_2") (pintype "passive"))
    )
    (net (code "119") (name "/PG12") (class "Default")
      (node (ref "SB191") (pin "1") (pinfunction "1_1") (pintype "passive"))
    )
    (net (code "120") (name "/PG13") (class "Default")
      (node (ref "SB194") (pin "2") (pinfunction "2_2") (pintype "passive"))
    )
    (net (code "121") (name "/PG14") (class "Default")
      (node (ref "CN12") (pin "61") (pinfunction "61_61") (pintype "passive"))
    )
    (net (code "122") (name "/PG15") (class "Default")
      (node (ref "CN11") (pin "64") (pinfunction "64_64") (pintype "passive"))
    )
    (net (code "124") (name "/PH0") (class "Default")
      (node (ref "SB147") (pin "1") (pinfunction "1_1") (pintype "passive"))
    )
    (net (code "125") (name "/PH1") (class "Default")
      (node (ref "SB156") (pin "1") (pinfunction "1_1") (pintype "passive"))
    )
    (net (code "126") (name "/PH3-BOOT0") (class "Default")
      (node (ref "CN11") (pin "7") (pinfunction "7_7") (pintype "passive"))
    )
    (net (code "128") (name "AGND") (class "Default")
      (node (ref "C45") (pin "2") (pinfunction "2_2") (pintype "passive"))
      (node (ref "CN10") (pin "3") (pinfunction "3_3") (pintype "passive"))
      (node (ref "CN12") (pin "32") (pinfunction "32_32") (pintype "passive"))
    )
    (net (code "129") (name "AVDD") (class "Default")
      (node (ref "CN10") (pin "1") (pinfunction "1_1") (pintype "passive"))
    )
    (net (code "130") (name "E5V") (class "Default")
      (node (ref "CN11") (pin "6") (pinfunction "6_6") (pintype "passive"))
    )
    (net (code "131") (name "GND") (class "Default")
      (node (ref "CN10") (pin "17") (pinfunction "17_17") (pintype "passive"))
      (node (ref "CN10") (pin "22") (pinfunction "22_22") (pintype "passive"))
      (node (ref "CN10") (pin "27") (pinfunction "27_27") (pintype "passive"))
      (node (ref "CN10") (pin "5") (pinfunction "5_5") (pintype "passive"))
      (node (ref "CN11") (pin "19") (pinfunction "19_19") (pintype "passive"))
      (node (ref "CN11") (pin "20") (pinfunction "20_20") (pintype "passive"))
      (node (ref "CN11") (pin "22") (pinfunction "22_22") (pintype "passive"))
      (node (ref "CN11") (pin "49") (pinfunction "49_49") (pintype "passive"))
      (node (ref "CN11") (pin "60") (pinfunction "60_60") (pintype "passive"))
      (node (ref "CN11") (pin "71") (pinfunction "71_71") (pintype "passive"))
      (node (ref "CN11") (pin "72") (pinfunction "72_72") (pintype "passive"))
      (node (ref "CN11") (pin "8") (pinfunction "8_8") (pintype "passive"))
      (node (ref "CN12") (pin "20") (pinfunction "20_20") (pintype "passive"))
      (node (ref "CN12") (pin "39") (pinfunction "39_39") (pintype "passive"))
      (node (ref "CN12") (pin "54") (pinfunction "54_54") (pintype "passive"))
      (node (ref "CN12") (pin "63") (pinfunction "63_63") (pintype "passive"))
      (node (ref "CN12") (pin "71") (pinfunction "71_71") (pintype "passive"))
      (node (ref "CN12") (pin "72") (pinfunction "72_72") (pintype "passive"))
      (node (ref "CN12") (pin "9") (pinfunction "9_9") (pintype "passive"))
      (node (ref "CN7") (pin "8") (pinfunction "8_8") (pintype "passive"))
      (node (ref "CN8") (pin "11") (pinfunction "11_11") (pintype "passive"))
      (node (ref "CN8") (pin "13") (pinfunction "13_13") (pintype "passive"))
      (node (ref "CN9") (pin "12") (pinfunction "12_12") (pintype "passive"))
      (node (ref "CN9") (pin "23") (pinfunction "23_23") (pintype "passive"))
      (node (ref "LD1") (pin "2") (pinfunction "K_2") (pintype "passive"))
      (node (ref "R36") (pin "2") (pinfunction "2_2") (pintype "passive"))
      (node (ref "U8") (pin "2") (pinfunction "VDD_2") (pintype "power_in"))
    )
    (net (code "132") (name "IOREF") (class "Default")
      (node (ref "CN11") (pin "12") (pinfunction "12_12") (pintype "passive"))
      (node (ref "CN8") (pin "3") (pinfunction "3_3") (pintype "passive"))
      (node (ref "SB110") (pin "2") (pinfunction "2_2") (pintype "passive"))
      (node (ref "SB111") (pin "2") (pinfunction "2_2") (pintype "passive"))
      (node (ref "SB112") (pin "2") (pinfunction "2_2") (pintype "passive"))
    )
    (net (code "133") (name "Net-(CN7-Pad9)") (class "Default")
      (node (ref "CN7") (pin "9") (pinfunction "9_9") (pintype "passive"))
      (node (ref "SB126") (pin "2") (pinfunction "2_2") (pintype "passive"))
    )
    (net (code "134") (name "Net-(CN7-Pad11)") (class "Default")
      (node (ref "CN7") (pin "11") (pinfunction "11_11") (pintype "passive"))
      (node (ref "SB128") (pin "2") (pinfunction "2_2") (pintype "passive"))
    )
    (net (code "135") (name "Net-(CN7-Pad17)") (class "Default")
      (node (ref "CN7") (pin "17") (pinfunction "17_17") (pintype "passive"))
      (node (ref "SB133") (pin "2") (pinfunction "2_2") (pintype "passive"))
    )
    (net (code "136") (name "Net-(CN7-Pad19)") (class "Default")
      (node (ref "CN7") (pin "19") (pinfunction "19_19") (pintype "passive"))
      (node (ref "SB140") (pin "2") (pinfunction "2_2") (pintype "passive"))
    )
    (net (code "137") (name "Net-(CN10-Pad13)") (class "Default")
      (node (ref "CN10") (pin "13") (pinfunction "13_13") (pintype "passive"))
      (node (ref "SB150") (pin "2") (pinfunction "2_2") (pintype "passive"))
    )
    (net (code "138") (name "Net-(CN10-Pad15)") (class "Default")
      (node (ref "CN10") (pin "15") (pinfunction "15_15") (pintype "passive"))
      (node (ref "SB155") (pin "2") (pinfunction "2_2") (pintype "passive"))
    )
    (net (code "139") (name "Net-(CN10-Pad19)") (class "Default")
      (node (ref "CN10") (pin "19") (pinfunction "19_19") (pintype "passive"))
      (node (ref "SB157") (pin "2") (pinfunction "2_2") (pintype "passive"))
    )
    (net (code "140") (name "Net-(CN10-Pad21)") (class "Default")
      (node (ref "CN10") (pin "21") (pinfunction "21_21") (pintype "passive"))
      (node (ref "SB159") (pin "2") (pinfunction "2_2") (pintype "passive"))
    )
    (net (code "141") (name "Net-(CN10-Pad23)") (class "Default")
      (node (ref "CN10") (pin "23") (pinfunction "23_23") (pintype "passive"))
      (node (ref "SB168") (pin "2") (pinfunction "2_2") (pintype "passive"))
    )
    (net (code "142") (name "Net-(CN10-Pad25)") (class "Default")
      (node (ref "CN10") (pin "25") (pinfunction "25_25") (pintype "passive"))
      (node (ref "SB170") (pin "2") (pinfunction "2_2") (pintype "passive"))
    )
    (net (code "143") (name "Net-(CN10-Pad26)") (class "Default")
      (node (ref "CN10") (pin "26") (pinfunction "26_26") (pintype "passive"))
      (node (ref "SB169") (pin "1") (pinfunction "1_1") (pintype "passive"))
    )
    (net (code "144") (name "Net-(CN10-Pad28)") (class "Default")
      (node (ref "CN10") (pin "28") (pinfunction "28_28") (pintype "passive"))
      (node (ref "SB177") (pin "1") (pinfunction "1_1") (pintype "passive"))
    )
    (net (code "145") (name "Net-(CN10-Pad29)") (class "Default")
      (node (ref "CN10") (pin "29") (pinfunction "29_29") (pintype "passive"))
      (node (ref "SB179") (pin "2") (pinfunction "2_2") (pintype "passive"))
    )
    (net (code "146") (name "Net-(CN10-Pad30)") (class "Default")
      (node (ref "CN10") (pin "30") (pinfunction "30_30") (pintype "passive"))
      (node (ref "SB180") (pin "1") (pinfunction "1_1") (pintype "passive"))
    )
    (net (code "147") (name "Net-(CN10-Pad31)") (class "Default")
      (node (ref "CN10") (pin "31") (pinfunction "31_31") (pintype "passive"))
      (node (ref "SB182") (pin "2") (pinfunction "2_2") (pintype "passive"))
    )
    (net (code "148") (name "Net-(CN10-Pad32)") (class "Default")
      (node (ref "CN10") (pin "32") (pinfunction "32_32") (pintype "passive"))
      (node (ref "SB188") (pin "1") (pinfunction "1_1") (pintype "passive"))
    )
    (net (code "149") (name "Net-(CN11-Pad25)") (class "Default")
      (node (ref "CN11") (pin "25") (pinfunction "25_25") (pintype "passive"))
      (node (ref "SB145") (pin "2") (pinfunction "2_2") (pintype "passive"))
    )
    (net (code "150") (name "Net-(CN11-Pad27)") (class "Default")
      (node (ref "CN11") (pin "27") (pinfunction "27_27") (pintype "passive"))
      (node (ref "SB146") (pin "2") (pinfunction "2_2") (pintype "passive"))
    )
    (net (code "151") (name "Net-(CN11-Pad29)") (class "Default")
      (node (ref "CN11") (pin "29") (pinfunction "29_29") (pintype "passive"))
      (node (ref "SB147") (pin "2") (pinfunction "2_2") (pintype "passive"))
    )
    (net (code "152") (name "Net-(CN11-Pad31)") (class "Default")
      (node (ref "CN11") (pin "31") (pinfunction "31_31") (pintype "passive"))
      (node (ref "SB156") (pin "2") (pinfunction "2_2") (pintype "passive"))
    )
    (net (code "153") (name "Net-(CN11-Pad34)") (class "Default")
      (node (ref "CN11") (pin "34") (pinfunction "34_34") (pintype "passive"))
      (node (ref "SB144") (pin "1") (pinfunction "1_1") (pintype "passive"))
    )
    (net (code "154") (name "Net-(CN11-Pad65)") (class "Default")
      (node (ref "CN11") (pin "65") (pinfunction "65_65") (pintype "passive"))
      (node (ref "SB191") (pin "2") (pinfunction "2_2") (pintype "passive"))
    )
    (net (code "155") (name "Net-(CN11-Pad66)") (class "Default")
      (node (ref "CN11") (pin "66") (pinfunction "66_66") (pintype "passive"))
      (node (ref "SB192") (pin "1") (pinfunction "1_1") (pintype "passive"))
    )
    (net (code "156") (name "Net-(CN11-Pad68)") (class "Default")
      (node (ref "CN11") (pin "68") (pinfunction "68_68") (pintype "passive"))
      (node (ref "SB194") (pin "1") (pinfunction "1_1") (pintype "passive"))
    )
    (net (code "157") (name "Net-(CN11-Pad70)") (class "Default")
      (node (ref "CN11") (pin "70") (pinfunction "70_70") (pintype "passive"))
      (node (ref "SB196") (pin "1") (pinfunction "1_1") (pintype "passive"))
    )
    (net (code "158") (name "Net-(CN12-Pad1)") (class "Default")
      (node (ref "CN12") (pin "1") (pinfunction "1_1") (pintype "passive"))
      (node (ref "SB136") (pin "2") (pinfunction "2_2") (pintype "passive"))
    )
    (net (code "159") (name "Net-(CN12-Pad2)") (class "Default")
      (node (ref "CN12") (pin "2") (pinfunction "2_2") (pintype "passive"))
      (node (ref "SB137") (pin "2") (pinfunction "2_2") (pintype "passive"))
    )
    (net (code "160") (name "Net-(CN12-Pad7)") (class "Default")
      (node (ref "CN12") (pin "7") (pinfunction "7_7") (pintype "passive"))
      (node (ref "CN7") (pin "6") (pinfunction "6_6") (pintype "passive"))
      (node (ref "SB119") (pin "2") (pinfunction "2_2") (pintype "passive"))
    )
    (net (code "161") (name "Net-(CN12-Pad66)") (class "Default")
      (node (ref "CN12") (pin "66") (pinfunction "66_66") (pintype "passive"))
      (node (ref "SB193") (pin "1") (pinfunction "1_1") (pintype "passive"))
    )
    (net (code "162") (name "Net-(CN12-Pad67)") (class "Default")
      (node (ref "CN12") (pin "67") (pinfunction "67_67") (pintype "passive"))
      (node (ref "SB195") (pin "2") (pinfunction "2_2") (pintype "passive"))
    )
    (net (code "163") (name "Net-(LD1-A)") (class "Default")
      (node (ref "LD1") (pin "1") (pinfunction "A_1") (pintype "passive"))
      (node (ref "R31") (pin "2") (pinfunction "2_2") (pintype "passive"))
    )
    (net (code "164") (name "Net-(R37-Pad2)") (class "Default")
      (node (ref "R37") (pin "2") (pinfunction "2_2") (pintype "passive"))
      (node (ref "SB123") (pin "1") (pinfunction "1_1") (pintype "passive"))
      (node (ref "SB124") (pin "2") (pinfunction "2_2") (pintype "passive"))
    )
    (net (code "165") (name "Net-(U8-IN+)") (class "Default")
      (node (ref "R36") (pin "1") (pinfunction "1_1") (pintype "passive"))
      (node (ref "R37") (pin "1") (pinfunction "1_1") (pintype "passive"))
      (node (ref "U8") (pin "1") (pinfunction "IN+_1") (pintype "input"))
    )
    (net (code "166") (name "Net-(U8-IN-)") (class "Default")
      (node (ref "R31") (pin "1") (pinfunction "1_1") (pintype "passive"))
      (node (ref "U8") (pin "3") (pinfunction "IN-_3") (pintype "input"))
      (node (ref "U8") (pin "4") (pinfunction "OUT_4") (pintype "output"))
    )
    (net (code "167") (name "U5V") (class "Default")
      (node (ref "CN12") (pin "8") (pinfunction "8_8") (pintype "passive"))
    )
    (net (code "168") (name "VBAT") (class "Default")
      (node (ref "CN11") (pin "33") (pinfunction "33_33") (pintype "passive"))
    )
    (net (code "169") (name "VDD") (class "Default")
      (node (ref "CN11") (pin "5") (pinfunction "5_5") (pintype "passive"))
    )
    (net (code "170") (name "VDD_MCU") (class "Default")
      (node (ref "SB112") (pin "1") (pinfunction "1_1") (pintype "passive"))
    )
    (net (code "171") (name "VIN") (class "Default")
      (node (ref "CN11") (pin "24") (pinfunction "24_24") (pintype "passive"))
      (node (ref "CN8") (pin "15") (pinfunction "15_15") (pintype "passive"))
    )
    (net (code "172") (name "VREF+") (class "Default")
      (node (ref "C45") (pin "1") (pinfunction "1_1") (pintype "passive"))
      (node (ref "SB119") (pin "1") (pinfunction "1_1") (pintype "passive"))
    )
    (net (code "173") (name "unconnected-(CN8-Pad1)") (class "Default")
      (node (ref "CN8") (pin "1") (pinfunction "1_1") (pintype "passive"))
    )
    (net (code "174") (name "unconnected-(CN11-Pad10)") (class "Default")
      (node (ref "CN11") (pin "10") (pinfunction "10_10") (pintype "passive"))
    )
    (net (code "175") (name "unconnected-(CN11-Pad26)") (class "Default")
      (node (ref "CN11") (pin "26") (pinfunction "26_26") (pintype "passive"))
    )
    (net (code "176") (name "unconnected-(CN11-Pad67)") (class "Default")
      (node (ref "CN11") (pin "67") (pinfunction "67_67") (pintype "passive"))
    )
  )
)
